# amc7135-by-4-15mm-led-aux-driver-mk-1_0.net
KiCad netlist of a schematic drawn in EAGLE
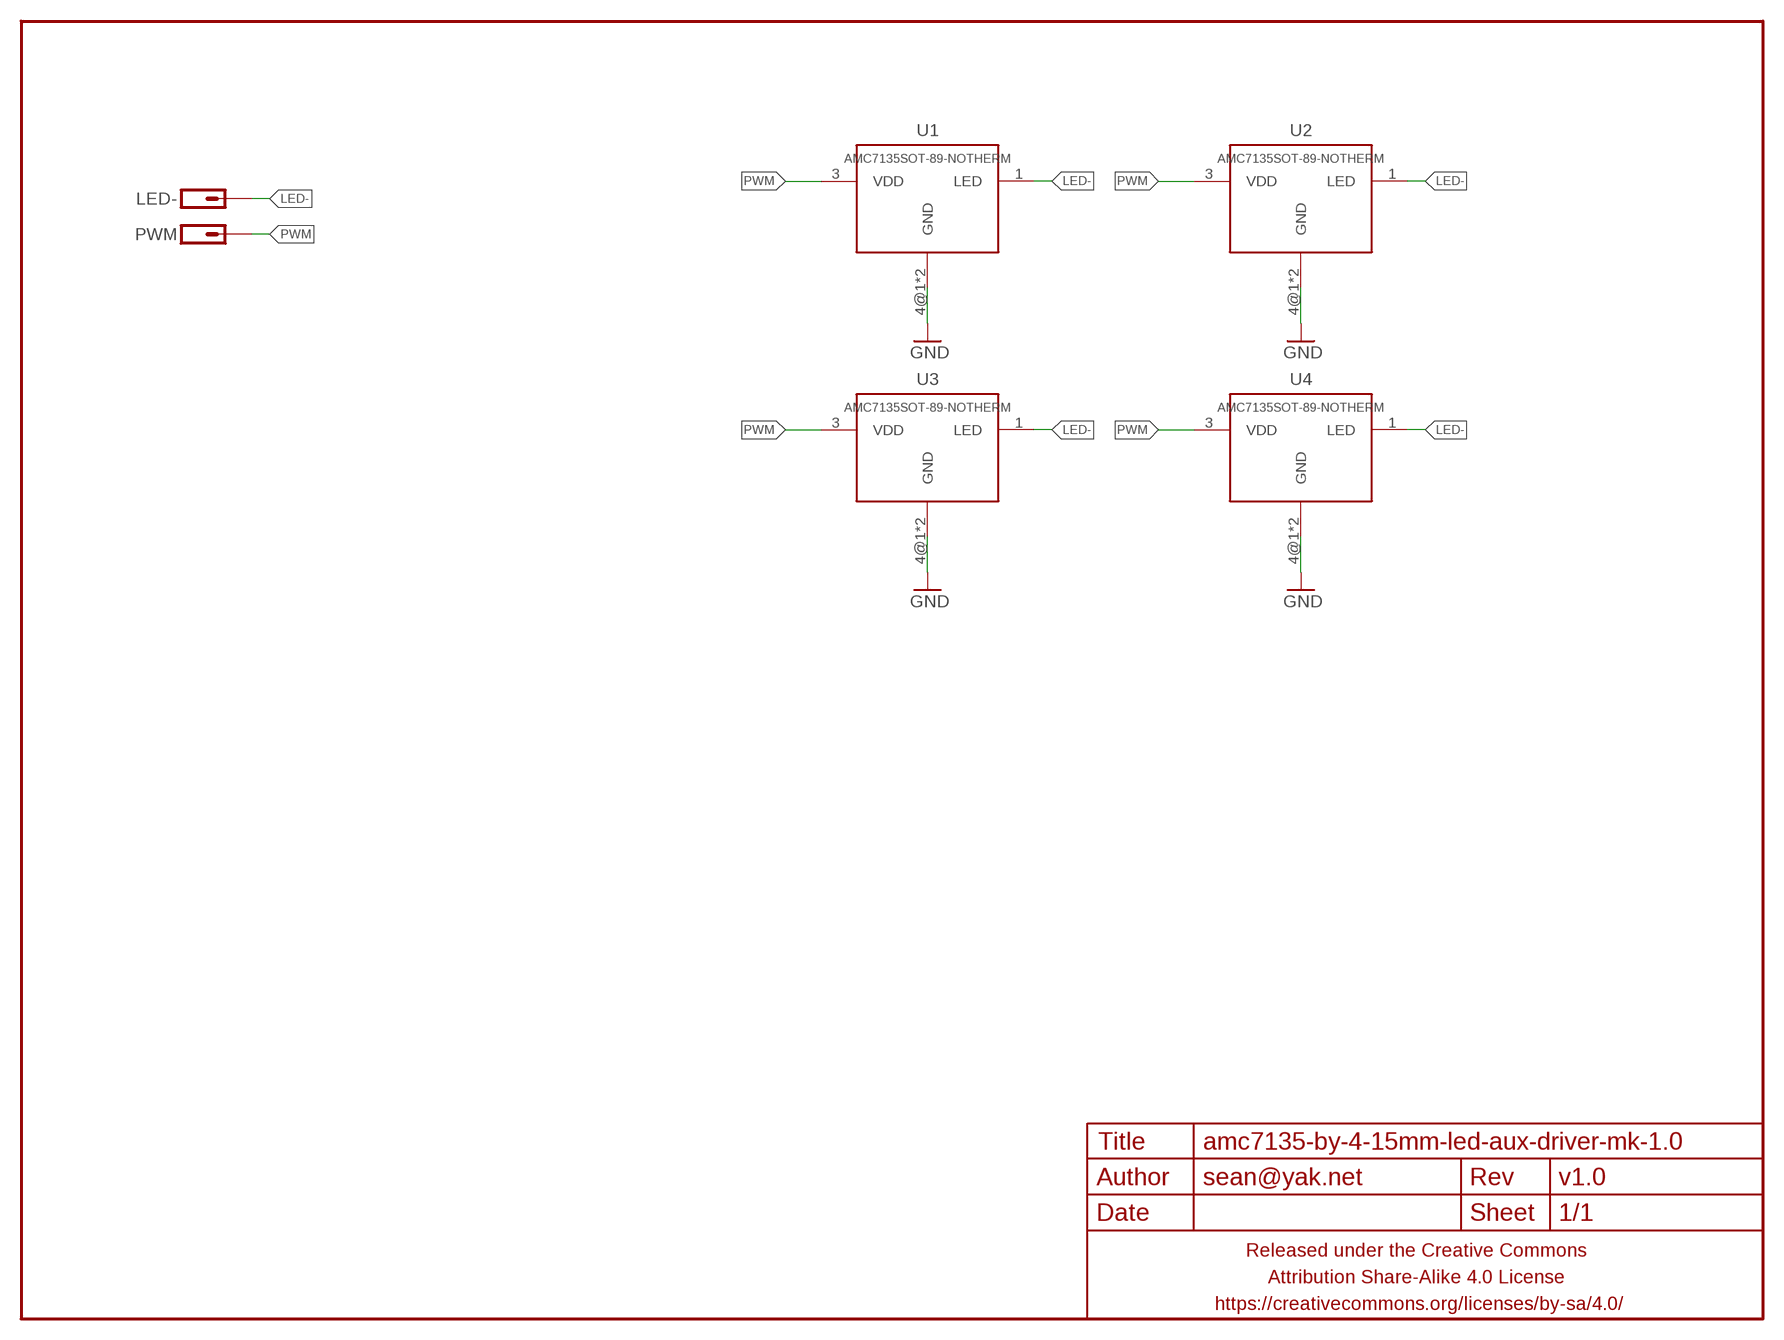
[diagram p0: schematic, sheet 1]

(export (version "E")
  (design (tool "Eeschema 10.0.6"))
  (components
    (comp (ref "FRAME1")
      (value "FRAME-LETTERNO_PACKAGE")
      (footprint "eagle-import:DUMMY")
      (fields (field (name "DESIGNER") "sean@yak.net") (field (name "VERSION") "v1.0"))
      (libsource (lib "eagle-import") (part "FRAME-LETTERNO_PACKAGE"))
    )
    (comp (ref "LED-")
      (value "M01SMD-1.25MM-DIA")
      (footprint "eagle-import:1X01-SMD-1.25MM-DIA-NS")
      (libsource (lib "eagle-import") (part "M01SMD-1.25MM-DIA"))
    )
    (comp (ref "PWM")
      (value "M01SMD-1.25MM-DIA")
      (footprint "eagle-import:1X01-SMD-1.25MM-DIA-NS")
      (libsource (lib "eagle-import") (part "M01SMD-1.25MM-DIA"))
    )
    (comp (ref "U1")
      (value "AMC7135SOT-89-NOTHERM")
      (footprint "eagle-import:SOT89-NOTHERM")
      (libsource (lib "eagle-import") (part "AMC7135SOT-89-NOTHERM"))
    )
    (comp (ref "U2")
      (value "AMC7135SOT-89-NOTHERM")
      (footprint "eagle-import:SOT89-NOTHERM")
      (libsource (lib "eagle-import") (part "AMC7135SOT-89-NOTHERM"))
    )
    (comp (ref "U3")
      (value "AMC7135SOT-89-NOTHERM")
      (footprint "eagle-import:SOT89-NOTHERM")
      (libsource (lib "eagle-import") (part "AMC7135SOT-89-NOTHERM"))
    )
    (comp (ref "U4")
      (value "AMC7135SOT-89-NOTHERM")
      (footprint "eagle-import:SOT89-NOTHERM")
      (libsource (lib "eagle-import") (part "AMC7135SOT-89-NOTHERM"))
    )
  )
  (nets
    (net (code "1") (name "GND") (class "Default")
      (node (ref "U1") (pin "4@1") (pinfunction "GND_4@1") (pintype "bidirectional"))
      (node (ref "U1") (pin "4@2") (pinfunction "GND_4@2") (pintype "bidirectional"))
      (node (ref "U2") (pin "4@1") (pinfunction "GND_4@1") (pintype "bidirectional"))
      (node (ref "U2") (pin "4@2") (pinfunction "GND_4@2") (pintype "bidirectional"))
      (node (ref "U3") (pin "4@1") (pinfunction "GND_4@1") (pintype "bidirectional"))
      (node (ref "U3") (pin "4@2") (pinfunction "GND_4@2") (pintype "bidirectional"))
      (node (ref "U4") (pin "4@1") (pinfunction "GND_4@1") (pintype "bidirectional"))
      (node (ref "U4") (pin "4@2") (pinfunction "GND_4@2") (pintype "bidirectional"))
    )
    (net (code "2") (name "LED-") (class "Default")
      (node (ref "LED-") (pin "P$1") (pinfunction "1_P$1") (pintype "passive"))
      (node (ref "U1") (pin "1") (pinfunction "LED_1") (pintype "bidirectional"))
      (node (ref "U2") (pin "1") (pinfunction "LED_1") (pintype "bidirectional"))
      (node (ref "U3") (pin "1") (pinfunction "LED_1") (pintype "bidirectional"))
      (node (ref "U4") (pin "1") (pinfunction "LED_1") (pintype "bidirectional"))
    )
    (net (code "3") (name "PWM") (class "Default")
      (node (ref "PWM") (pin "P$1") (pinfunction "1_P$1") (pintype "passive"))
      (node (ref "U1") (pin "3") (pinfunction "VDD_3") (pintype "bidirectional"))
      (node (ref "U2") (pin "3") (pinfunction "VDD_3") (pintype "bidirectional"))
      (node (ref "U3") (pin "3") (pinfunction "VDD_3") (pintype "bidirectional"))
      (node (ref "U4") (pin "3") (pinfunction "VDD_3") (pintype "bidirectional"))
    )
  )
)
